# PC104_52-52.net
KiCad netlist of a schematic drawn in Altium Designer
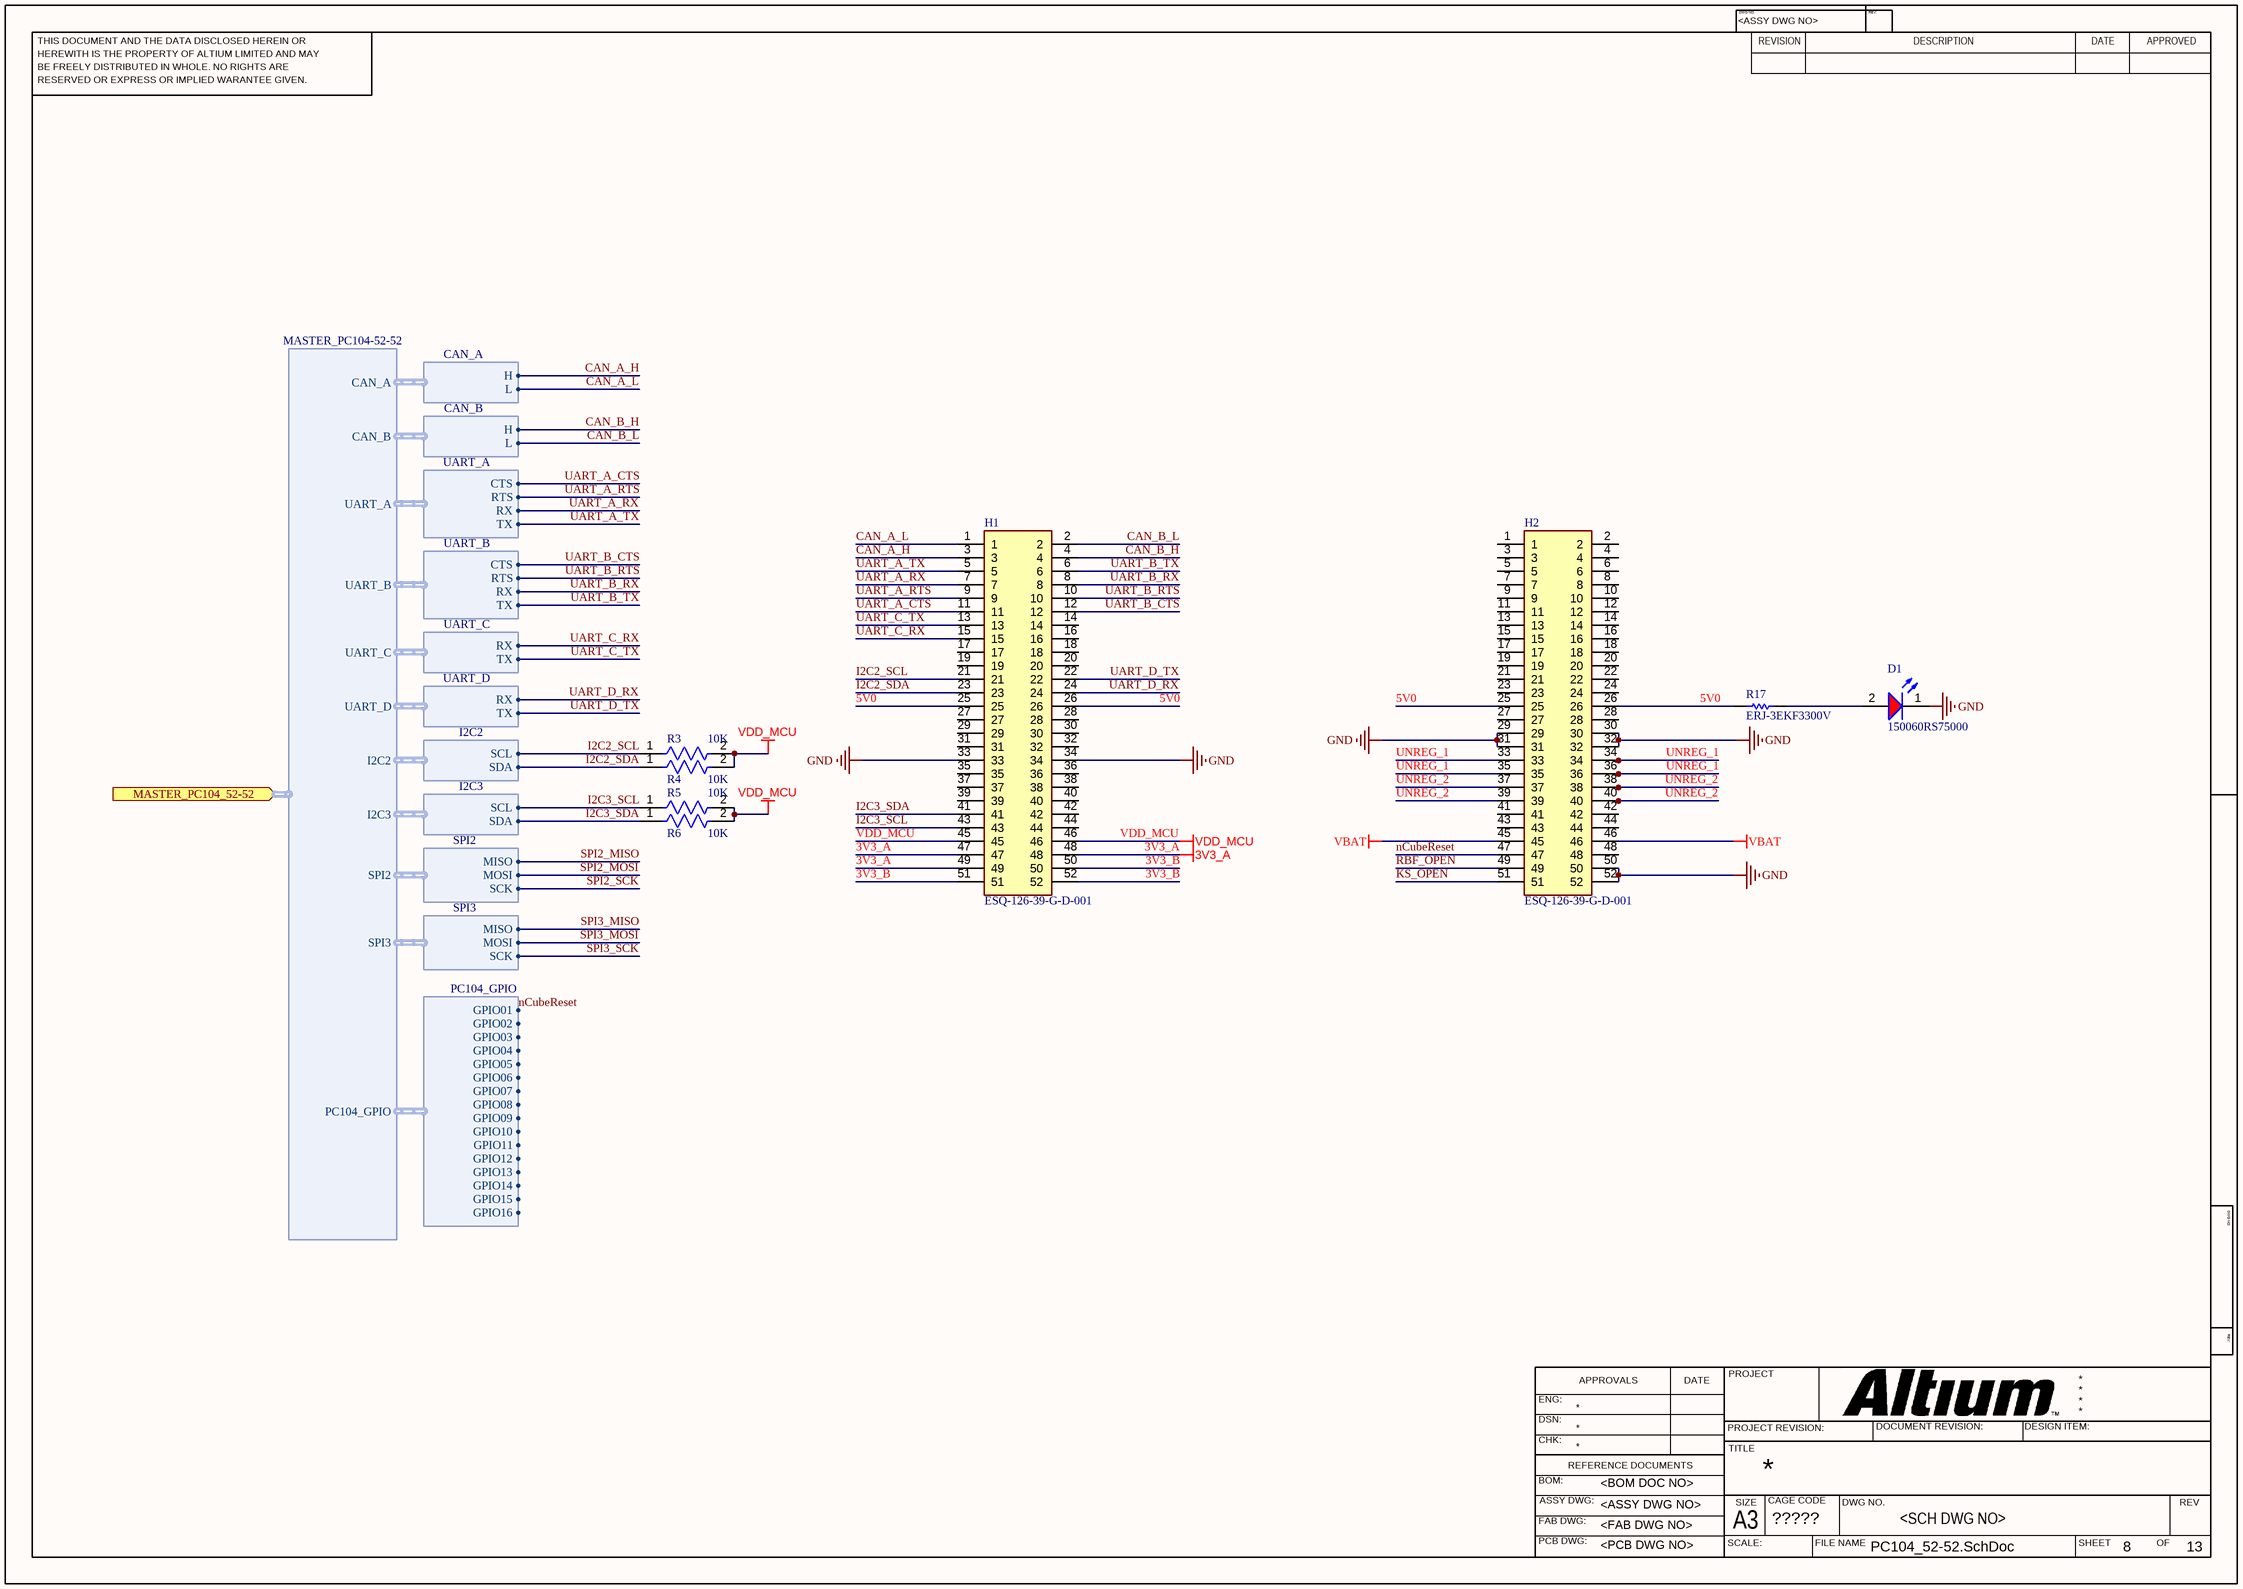
[diagram p0: PC104_52-52.SchDoc]

(export (version "E")
  (design (tool "Eeschema 10.0.6"))
  (components
    (comp (ref "D1")
      (value "150060RS75000")
      (footprint "WL-SMCW_0603_150060xx75000")
      (description "LED Low-Power Uni-Color Red 630nm 2V 2-Pin Chip 0603(1608Metric) T/R")
      (libsource (lib "Altium Content Vault") (part "LED_Red_2A-1K"))
    )
    (comp (ref "H1")
      (value "ESQ-126-39-G-D-001")
      (footprint "RHDR52W64P254_2X26_6654X495X1135P")
      (description "PC / 104 Connectors Elevated Socket Strip")
      (fields (field (name "MOUSER PART NUMBER") "200-ESQ12639GD001"))
      (libsource (lib "Hitesh Bhoyar") (part "ESQ-126-39-G-D-001"))
    )
    (comp (ref "H2")
      (value "ESQ-126-39-G-D-001")
      (footprint "RHDR52W64P254_2X26_6654X495X1135P")
      (description "PC / 104 Connectors Elevated Socket Strip")
      (fields (field (name "MOUSER PART NUMBER") "200-ESQ12639GD001"))
      (libsource (lib "Hitesh Bhoyar") (part "ESQ-126-39-G-D-001"))
    )
    (comp (ref "R3")
      (value "10K")
      (footprint "FP-RK73B1J-MFG")
      (description "RES 10K OHM 5% 1/10W 0603")
      (fields (field (name "TOLERANCE") "5%"))
      (libsource (lib "Altium Content Vault") (part "1029c3af85768c4190bb7ad29bc67b5"))
    )
    (comp (ref "R4")
      (value "10K")
      (footprint "FP-RK73B1J-MFG")
      (description "RES 10K OHM 5% 1/10W 0603")
      (fields (field (name "TOLERANCE") "5%"))
      (libsource (lib "Altium Content Vault") (part "1029c3af85768c4190bb7ad29bc67b5"))
    )
    (comp (ref "R5")
      (value "10K")
      (footprint "FP-RK73B1J-MFG")
      (description "RES 10K OHM 5% 1/10W 0603")
      (fields (field (name "TOLERANCE") "5%"))
      (libsource (lib "Altium Content Vault") (part "1029c3af85768c4190bb7ad29bc67b5"))
    )
    (comp (ref "R6")
      (value "10K")
      (footprint "FP-RK73B1J-MFG")
      (description "RES 10K OHM 5% 1/10W 0603")
      (fields (field (name "TOLERANCE") "5%"))
      (libsource (lib "Altium Content Vault") (part "1029c3af85768c4190bb7ad29bc67b5"))
    )
    (comp (ref "R17")
      (value "ERJ-3EKF3300V")
      (footprint "RESC1608X55X30LL15T15")
      (description "Chip Resistor, 330 Ohm, +/- 1%, 0.1 W, -55 to 155 degC, 0603 (1608 Metric), RoHS, Tape and Reel")
      (libsource (lib "Altium Content Vault") (part "RES-2"))
    )
  )
  (nets
    (net (code "13") (name "/3V3_B") (class "Default")
      (node (ref "H1") (pin "50") (pinfunction "50_50") (pintype "passive"))
      (node (ref "H1") (pin "51") (pinfunction "51_51") (pintype "passive"))
      (node (ref "H1") (pin "52") (pinfunction "52_52") (pintype "passive"))
    )
    (net (code "14") (name "/5V0") (class "Default")
      (node (ref "H1") (pin "25") (pinfunction "25_25") (pintype "passive"))
      (node (ref "H1") (pin "26") (pinfunction "26_26") (pintype "passive"))
      (node (ref "H2") (pin "25") (pinfunction "25_25") (pintype "passive"))
      (node (ref "H2") (pin "26") (pinfunction "26_26") (pintype "passive"))
      (node (ref "R17") (pin "1") (pinfunction "1_1") (pintype "passive"))
    )
    (net (code "15") (name "/CAN_A_H") (class "Default")
      (node (ref "H1") (pin "3") (pinfunction "3_3") (pintype "passive"))
    )
    (net (code "16") (name "/CAN_A_L") (class "Default")
      (node (ref "H1") (pin "1") (pinfunction "1_1") (pintype "passive"))
    )
    (net (code "17") (name "/CAN_B_H") (class "Default")
      (node (ref "H1") (pin "4") (pinfunction "4_4") (pintype "passive"))
    )
    (net (code "18") (name "/CAN_B_L") (class "Default")
      (node (ref "H1") (pin "2") (pinfunction "2_2") (pintype "passive"))
    )
    (net (code "19") (name "/I2C2_SCL") (class "Default")
      (node (ref "H1") (pin "21") (pinfunction "21_21") (pintype "passive"))
      (node (ref "R3") (pin "1") (pinfunction "1_1") (pintype "passive"))
    )
    (net (code "20") (name "/I2C2_SDA") (class "Default")
      (node (ref "H1") (pin "23") (pinfunction "23_23") (pintype "passive"))
      (node (ref "R4") (pin "1") (pinfunction "1_1") (pintype "passive"))
    )
    (net (code "21") (name "/I2C3_SCL") (class "Default")
      (node (ref "H1") (pin "43") (pinfunction "43_43") (pintype "passive"))
      (node (ref "R5") (pin "1") (pinfunction "1_1") (pintype "passive"))
    )
    (net (code "22") (name "/I2C3_SDA") (class "Default")
      (node (ref "H1") (pin "41") (pinfunction "41_41") (pintype "passive"))
      (node (ref "R6") (pin "1") (pinfunction "1_1") (pintype "passive"))
    )
    (net (code "23") (name "/KS_OPEN") (class "Default")
      (node (ref "H2") (pin "51") (pinfunction "51_51") (pintype "passive"))
    )
    (net (code "25") (name "/RBF_OPEN") (class "Default")
      (node (ref "H2") (pin "49") (pinfunction "49_49") (pintype "passive"))
    )
    (net (code "32") (name "/UART_A_CTS") (class "Default")
      (node (ref "H1") (pin "11") (pinfunction "11_11") (pintype "passive"))
    )
    (net (code "33") (name "/UART_A_RTS") (class "Default")
      (node (ref "H1") (pin "9") (pinfunction "9_9") (pintype "passive"))
    )
    (net (code "34") (name "/UART_A_RX") (class "Default")
      (node (ref "H1") (pin "7") (pinfunction "7_7") (pintype "passive"))
    )
    (net (code "35") (name "/UART_A_TX") (class "Default")
      (node (ref "H1") (pin "5") (pinfunction "5_5") (pintype "passive"))
    )
    (net (code "36") (name "/UART_B_CTS") (class "Default")
      (node (ref "H1") (pin "12") (pinfunction "12_12") (pintype "passive"))
    )
    (net (code "37") (name "/UART_B_RTS") (class "Default")
      (node (ref "H1") (pin "10") (pinfunction "10_10") (pintype "passive"))
    )
    (net (code "38") (name "/UART_B_RX") (class "Default")
      (node (ref "H1") (pin "8") (pinfunction "8_8") (pintype "passive"))
    )
    (net (code "39") (name "/UART_B_TX") (class "Default")
      (node (ref "H1") (pin "6") (pinfunction "6_6") (pintype "passive"))
    )
    (net (code "40") (name "/UART_C_RX") (class "Default")
      (node (ref "H1") (pin "15") (pinfunction "15_15") (pintype "passive"))
    )
    (net (code "41") (name "/UART_C_TX") (class "Default")
      (node (ref "H1") (pin "13") (pinfunction "13_13") (pintype "passive"))
    )
    (net (code "42") (name "/UART_D_RX") (class "Default")
      (node (ref "H1") (pin "24") (pinfunction "24_24") (pintype "passive"))
    )
    (net (code "43") (name "/UART_D_TX") (class "Default")
      (node (ref "H1") (pin "22") (pinfunction "22_22") (pintype "passive"))
    )
    (net (code "44") (name "/UNREG_1") (class "Default")
      (node (ref "H2") (pin "33") (pinfunction "33_33") (pintype "passive"))
      (node (ref "H2") (pin "34") (pinfunction "34_34") (pintype "passive"))
      (node (ref "H2") (pin "35") (pinfunction "35_35") (pintype "passive"))
      (node (ref "H2") (pin "36") (pinfunction "36_36") (pintype "passive"))
    )
    (net (code "45") (name "/UNREG_2") (class "Default")
      (node (ref "H2") (pin "37") (pinfunction "37_37") (pintype "passive"))
      (node (ref "H2") (pin "38") (pinfunction "38_38") (pintype "passive"))
      (node (ref "H2") (pin "39") (pinfunction "39_39") (pintype "passive"))
      (node (ref "H2") (pin "40") (pinfunction "40_40") (pintype "passive"))
    )
    (net (code "46") (name "/nCubeReset") (class "Default")
      (node (ref "H2") (pin "47") (pinfunction "47_47") (pintype "passive"))
    )
    (net (code "58") (name "3V3_A") (class "Default")
      (node (ref "H1") (pin "47") (pinfunction "47_47") (pintype "passive"))
      (node (ref "H1") (pin "48") (pinfunction "48_48") (pintype "passive"))
      (node (ref "H1") (pin "49") (pinfunction "49_49") (pintype "passive"))
    )
    (net (code "59") (name "GND") (class "Default")
      (node (ref "D1") (pin "1") (pinfunction "K_1") (pintype "passive"))
      (node (ref "H1") (pin "33") (pinfunction "33_33") (pintype "passive"))
      (node (ref "H1") (pin "34") (pinfunction "34_34") (pintype "passive"))
      (node (ref "H2") (pin "29") (pinfunction "29_29") (pintype "passive"))
      (node (ref "H2") (pin "30") (pinfunction "30_30") (pintype "passive"))
      (node (ref "H2") (pin "31") (pinfunction "31_31") (pintype "passive"))
      (node (ref "H2") (pin "32") (pinfunction "32_32") (pintype "passive"))
      (node (ref "H2") (pin "50") (pinfunction "50_50") (pintype "passive"))
      (node (ref "H2") (pin "52") (pinfunction "52_52") (pintype "passive"))
    )
    (net (code "60") (name "Net-(D1-A)") (class "Default")
      (node (ref "D1") (pin "2") (pinfunction "A_2") (pintype "passive"))
      (node (ref "R17") (pin "2") (pinfunction "2_2") (pintype "passive"))
    )
    (net (code "61") (name "VBAT") (class "Default")
      (node (ref "H2") (pin "45") (pinfunction "45_45") (pintype "passive"))
      (node (ref "H2") (pin "46") (pinfunction "46_46") (pintype "passive"))
    )
    (net (code "62") (name "VDD_MCU") (class "Default")
      (node (ref "H1") (pin "45") (pinfunction "45_45") (pintype "passive"))
      (node (ref "H1") (pin "46") (pinfunction "46_46") (pintype "passive"))
      (node (ref "R3") (pin "2") (pinfunction "2_2") (pintype "passive"))
      (node (ref "R4") (pin "2") (pinfunction "2_2") (pintype "passive"))
      (node (ref "R5") (pin "2") (pinfunction "2_2") (pintype "passive"))
      (node (ref "R6") (pin "2") (pinfunction "2_2") (pintype "passive"))
    )
    (net (code "63") (name "unconnected-(H1-Pad14)") (class "Default")
      (node (ref "H1") (pin "14") (pinfunction "14_14") (pintype "passive"))
    )
    (net (code "64") (name "unconnected-(H1-Pad16)") (class "Default")
      (node (ref "H1") (pin "16") (pinfunction "16_16") (pintype "passive"))
    )
    (net (code "65") (name "unconnected-(H1-Pad17)") (class "Default")
      (node (ref "H1") (pin "17") (pinfunction "17_17") (pintype "passive"))
    )
    (net (code "66") (name "unconnected-(H1-Pad18)") (class "Default")
      (node (ref "H1") (pin "18") (pinfunction "18_18") (pintype "passive"))
    )
    (net (code "67") (name "unconnected-(H1-Pad19)") (class "Default")
      (node (ref "H1") (pin "19") (pinfunction "19_19") (pintype "passive"))
    )
    (net (code "68") (name "unconnected-(H1-Pad20)") (class "Default")
      (node (ref "H1") (pin "20") (pinfunction "20_20") (pintype "passive"))
    )
    (net (code "69") (name "unconnected-(H1-Pad27)") (class "Default")
      (node (ref "H1") (pin "27") (pinfunction "27_27") (pintype "passive"))
    )
    (net (code "70") (name "unconnected-(H1-Pad28)") (class "Default")
      (node (ref "H1") (pin "28") (pinfunction "28_28") (pintype "passive"))
    )
    (net (code "71") (name "unconnected-(H1-Pad29)") (class "Default")
      (node (ref "H1") (pin "29") (pinfunction "29_29") (pintype "passive"))
    )
    (net (code "72") (name "unconnected-(H1-Pad30)") (class "Default")
      (node (ref "H1") (pin "30") (pinfunction "30_30") (pintype "passive"))
    )
    (net (code "73") (name "unconnected-(H1-Pad31)") (class "Default")
      (node (ref "H1") (pin "31") (pinfunction "31_31") (pintype "passive"))
    )
    (net (code "74") (name "unconnected-(H1-Pad32)") (class "Default")
      (node (ref "H1") (pin "32") (pinfunction "32_32") (pintype "passive"))
    )
    (net (code "75") (name "unconnected-(H1-Pad35)") (class "Default")
      (node (ref "H1") (pin "35") (pinfunction "35_35") (pintype "passive"))
    )
    (net (code "76") (name "unconnected-(H1-Pad36)") (class "Default")
      (node (ref "H1") (pin "36") (pinfunction "36_36") (pintype "passive"))
    )
    (net (code "77") (name "unconnected-(H1-Pad37)") (class "Default")
      (node (ref "H1") (pin "37") (pinfunction "37_37") (pintype "passive"))
    )
    (net (code "78") (name "unconnected-(H1-Pad38)") (class "Default")
      (node (ref "H1") (pin "38") (pinfunction "38_38") (pintype "passive"))
    )
    (net (code "79") (name "unconnected-(H1-Pad39)") (class "Default")
      (node (ref "H1") (pin "39") (pinfunction "39_39") (pintype "passive"))
    )
    (net (code "80") (name "unconnected-(H1-Pad40)") (class "Default")
      (node (ref "H1") (pin "40") (pinfunction "40_40") (pintype "passive"))
    )
    (net (code "81") (name "unconnected-(H1-Pad42)") (class "Default")
      (node (ref "H1") (pin "42") (pinfunction "42_42") (pintype "passive"))
    )
    (net (code "82") (name "unconnected-(H1-Pad44)") (class "Default")
      (node (ref "H1") (pin "44") (pinfunction "44_44") (pintype "passive"))
    )
    (net (code "83") (name "unconnected-(H2-Pad1)") (class "Default")
      (node (ref "H2") (pin "1") (pinfunction "1_1") (pintype "passive"))
    )
    (net (code "84") (name "unconnected-(H2-Pad2)") (class "Default")
      (node (ref "H2") (pin "2") (pinfunction "2_2") (pintype "passive"))
    )
    (net (code "85") (name "unconnected-(H2-Pad3)") (class "Default")
      (node (ref "H2") (pin "3") (pinfunction "3_3") (pintype "passive"))
    )
    (net (code "86") (name "unconnected-(H2-Pad4)") (class "Default")
      (node (ref "H2") (pin "4") (pinfunction "4_4") (pintype "passive"))
    )
    (net (code "87") (name "unconnected-(H2-Pad5)") (class "Default")
      (node (ref "H2") (pin "5") (pinfunction "5_5") (pintype "passive"))
    )
    (net (code "88") (name "unconnected-(H2-Pad6)") (class "Default")
      (node (ref "H2") (pin "6") (pinfunction "6_6") (pintype "passive"))
    )
    (net (code "89") (name "unconnected-(H2-Pad7)") (class "Default")
      (node (ref "H2") (pin "7") (pinfunction "7_7") (pintype "passive"))
    )
    (net (code "90") (name "unconnected-(H2-Pad8)") (class "Default")
      (node (ref "H2") (pin "8") (pinfunction "8_8") (pintype "passive"))
    )
    (net (code "91") (name "unconnected-(H2-Pad9)") (class "Default")
      (node (ref "H2") (pin "9") (pinfunction "9_9") (pintype "passive"))
    )
    (net (code "92") (name "unconnected-(H2-Pad10)") (class "Default")
      (node (ref "H2") (pin "10") (pinfunction "10_10") (pintype "passive"))
    )
    (net (code "93") (name "unconnected-(H2-Pad11)") (class "Default")
      (node (ref "H2") (pin "11") (pinfunction "11_11") (pintype "passive"))
    )
    (net (code "94") (name "unconnected-(H2-Pad12)") (class "Default")
      (node (ref "H2") (pin "12") (pinfunction "12_12") (pintype "passive"))
    )
    (net (code "95") (name "unconnected-(H2-Pad13)") (class "Default")
      (node (ref "H2") (pin "13") (pinfunction "13_13") (pintype "passive"))
    )
    (net (code "96") (name "unconnected-(H2-Pad14)") (class "Default")
      (node (ref "H2") (pin "14") (pinfunction "14_14") (pintype "passive"))
    )
    (net (code "97") (name "unconnected-(H2-Pad15)") (class "Default")
      (node (ref "H2") (pin "15") (pinfunction "15_15") (pintype "passive"))
    )
    (net (code "98") (name "unconnected-(H2-Pad16)") (class "Default")
      (node (ref "H2") (pin "16") (pinfunction "16_16") (pintype "passive"))
    )
    (net (code "99") (name "unconnected-(H2-Pad17)") (class "Default")
      (node (ref "H2") (pin "17") (pinfunction "17_17") (pintype "passive"))
    )
    (net (code "100") (name "unconnected-(H2-Pad18)") (class "Default")
      (node (ref "H2") (pin "18") (pinfunction "18_18") (pintype "passive"))
    )
    (net (code "101") (name "unconnected-(H2-Pad19)") (class "Default")
      (node (ref "H2") (pin "19") (pinfunction "19_19") (pintype "passive"))
    )
    (net (code "102") (name "unconnected-(H2-Pad20)") (class "Default")
      (node (ref "H2") (pin "20") (pinfunction "20_20") (pintype "passive"))
    )
    (net (code "103") (name "unconnected-(H2-Pad21)") (class "Default")
      (node (ref "H2") (pin "21") (pinfunction "21_21") (pintype "passive"))
    )
    (net (code "104") (name "unconnected-(H2-Pad22)") (class "Default")
      (node (ref "H2") (pin "22") (pinfunction "22_22") (pintype "passive"))
    )
    (net (code "105") (name "unconnected-(H2-Pad23)") (class "Default")
      (node (ref "H2") (pin "23") (pinfunction "23_23") (pintype "passive"))
    )
    (net (code "106") (name "unconnected-(H2-Pad24)") (class "Default")
      (node (ref "H2") (pin "24") (pinfunction "24_24") (pintype "passive"))
    )
    (net (code "107") (name "unconnected-(H2-Pad27)") (class "Default")
      (node (ref "H2") (pin "27") (pinfunction "27_27") (pintype "passive"))
    )
    (net (code "108") (name "unconnected-(H2-Pad28)") (class "Default")
      (node (ref "H2") (pin "28") (pinfunction "28_28") (pintype "passive"))
    )
    (net (code "109") (name "unconnected-(H2-Pad41)") (class "Default")
      (node (ref "H2") (pin "41") (pinfunction "41_41") (pintype "passive"))
    )
    (net (code "110") (name "unconnected-(H2-Pad42)") (class "Default")
      (node (ref "H2") (pin "42") (pinfunction "42_42") (pintype "passive"))
    )
    (net (code "111") (name "unconnected-(H2-Pad43)") (class "Default")
      (node (ref "H2") (pin "43") (pinfunction "43_43") (pintype "passive"))
    )
    (net (code "112") (name "unconnected-(H2-Pad44)") (class "Default")
      (node (ref "H2") (pin "44") (pinfunction "44_44") (pintype "passive"))
    )
    (net (code "113") (name "unconnected-(H2-Pad48)") (class "Default")
      (node (ref "H2") (pin "48") (pinfunction "48_48") (pintype "passive"))
    )
  )
)
